# md_v02.net
KiCad netlist of a schematic drawn in EAGLE
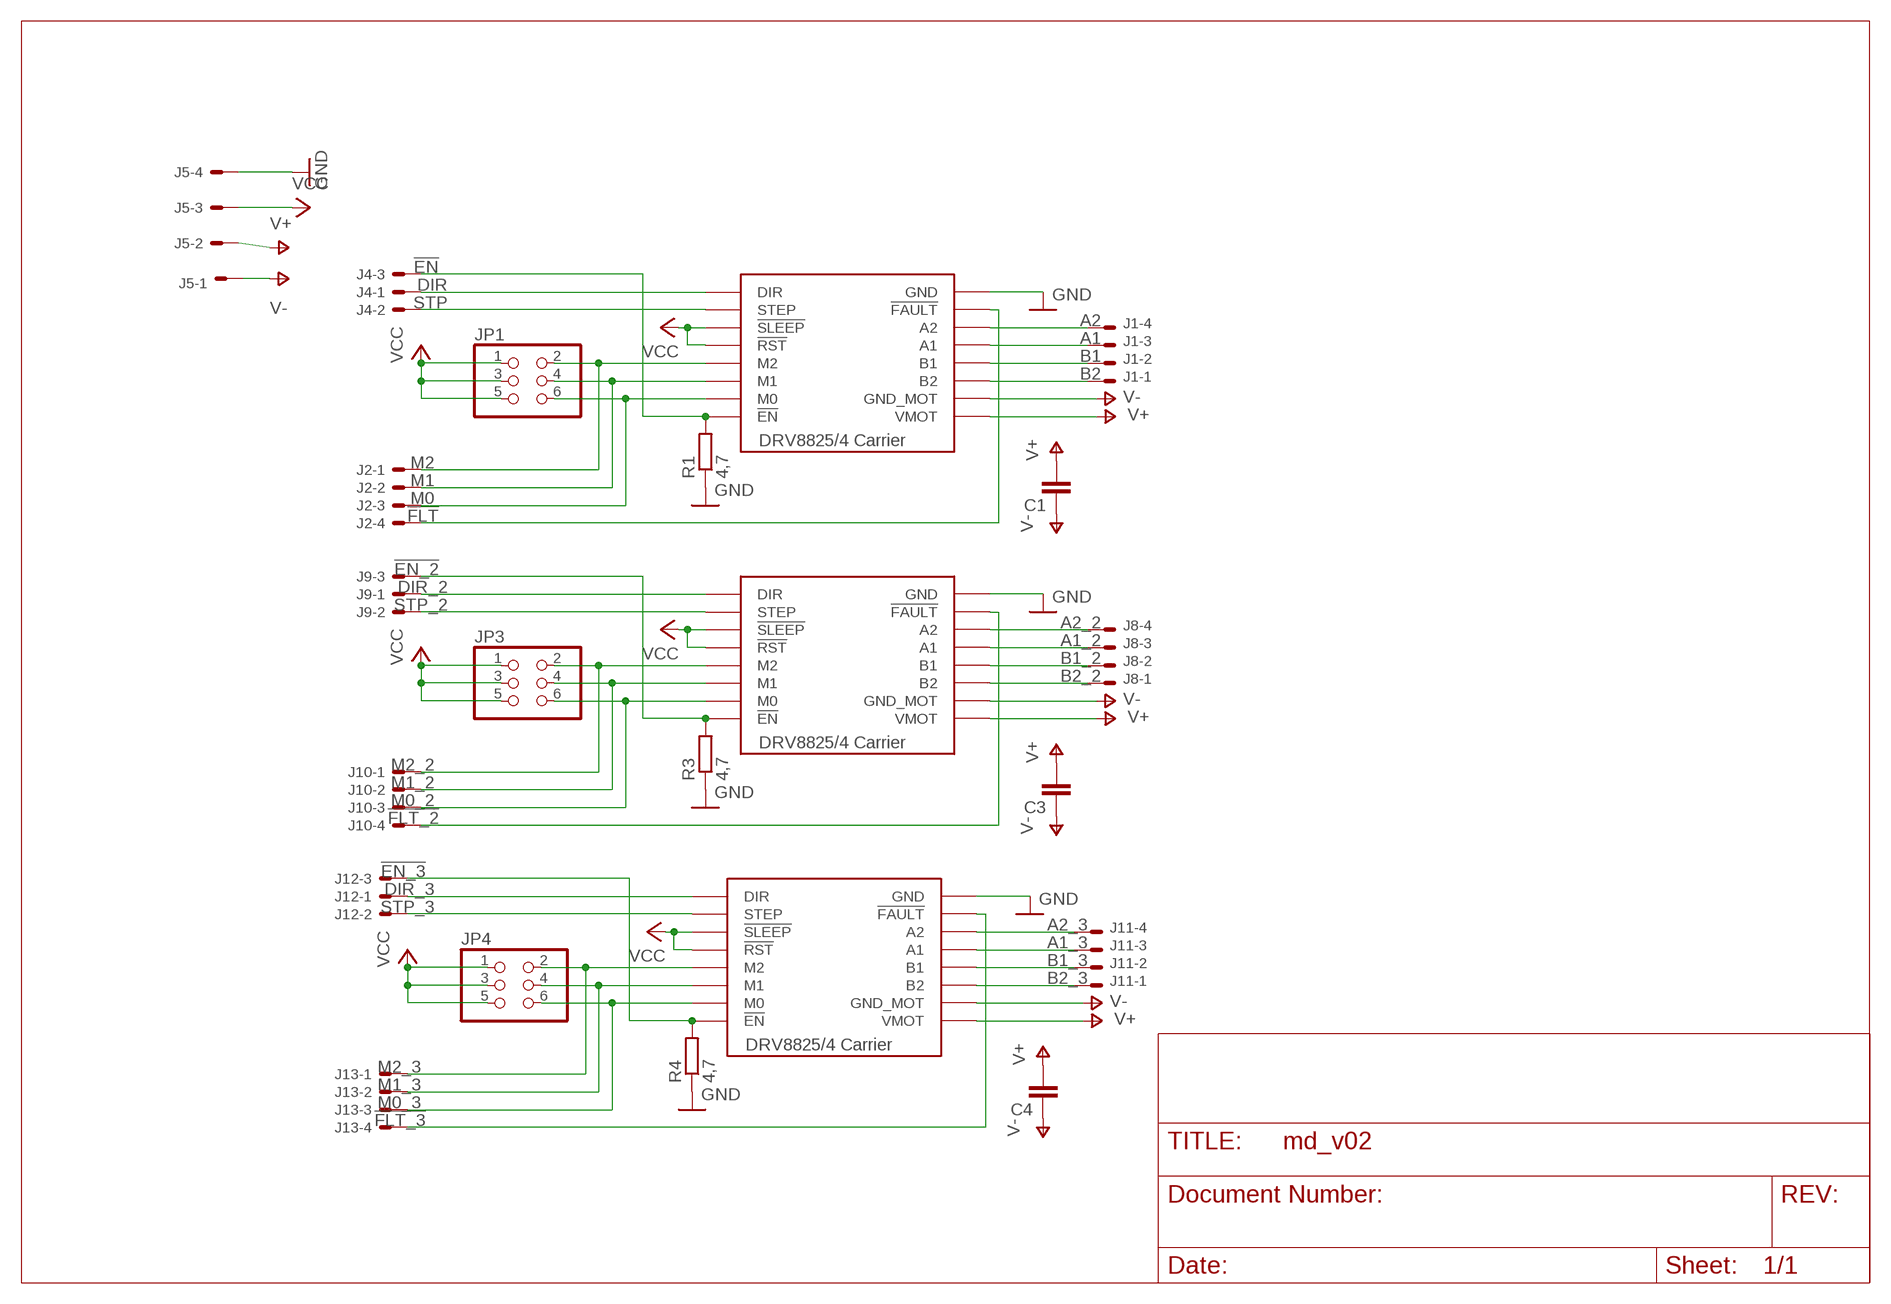
[diagram p0: schematic, sheet 1]

(export (version "E")
  (design (tool "Eeschema 10.0.6"))
  (components
    (comp (ref "C1")
      (value "C-EU050-035X075")
      (footprint "eagle-import:C050-035X075")
      (libsource (lib "eagle-import") (part "C-EU050-035X075"))
    )
    (comp (ref "C3")
      (value "C-EU050-035X075")
      (footprint "eagle-import:C050-035X075")
      (libsource (lib "eagle-import") (part "C-EU050-035X075"))
    )
    (comp (ref "C4")
      (value "C-EU050-035X075")
      (footprint "eagle-import:C050-035X075")
      (libsource (lib "eagle-import") (part "C-EU050-035X075"))
    )
    (comp (ref "J1")
      (value "22-27-2041-04")
      (footprint "eagle-import:6410-04")
      (fields (field (name "MF") "MOLEX"))
      (libsource (lib "eagle-import") (part "22-?-0427-2041"))
    )
    (comp (ref "J2")
      (value "22-27-2041-04")
      (footprint "eagle-import:6410-04")
      (fields (field (name "MF") "MOLEX"))
      (libsource (lib "eagle-import") (part "22-?-0427-2041"))
    )
    (comp (ref "J4")
      (value "22-27-2031-03")
      (footprint "eagle-import:6410-03")
      (fields (field (name "MF") "MOLEX"))
      (libsource (lib "eagle-import") (part "22-?-0327-2031"))
    )
    (comp (ref "J5")
      (value "22-27-2041-04")
      (footprint "eagle-import:6410-04")
      (fields (field (name "MF") "MOLEX"))
      (libsource (lib "eagle-import") (part "22-?-0427-2041"))
    )
    (comp (ref "J8")
      (value "22-27-2041-04")
      (footprint "eagle-import:6410-04")
      (fields (field (name "MF") "MOLEX"))
      (libsource (lib "eagle-import") (part "22-?-0427-2041"))
    )
    (comp (ref "J9")
      (value "22-27-2031-03")
      (footprint "eagle-import:6410-03")
      (fields (field (name "MF") "MOLEX"))
      (libsource (lib "eagle-import") (part "22-?-0327-2031"))
    )
    (comp (ref "J10")
      (value "22-27-2041-04")
      (footprint "eagle-import:6410-04")
      (fields (field (name "MF") "MOLEX"))
      (libsource (lib "eagle-import") (part "22-?-0427-2041"))
    )
    (comp (ref "J11")
      (value "22-27-2041-04")
      (footprint "eagle-import:6410-04")
      (fields (field (name "MF") "MOLEX"))
      (libsource (lib "eagle-import") (part "22-?-0427-2041"))
    )
    (comp (ref "J12")
      (value "22-27-2031-03")
      (footprint "eagle-import:6410-03")
      (fields (field (name "MF") "MOLEX"))
      (libsource (lib "eagle-import") (part "22-?-0327-2031"))
    )
    (comp (ref "J13")
      (value "22-27-2041-04")
      (footprint "eagle-import:6410-04")
      (fields (field (name "MF") "MOLEX"))
      (libsource (lib "eagle-import") (part "22-?-0427-2041"))
    )
    (comp (ref "JP1")
      (value "PINHD-2X3")
      (footprint "eagle-import:2X03")
      (libsource (lib "eagle-import") (part "PINHD-2X3"))
    )
    (comp (ref "JP3")
      (value "PINHD-2X3")
      (footprint "eagle-import:2X03")
      (libsource (lib "eagle-import") (part "PINHD-2X3"))
    )
    (comp (ref "JP4")
      (value "PINHD-2X3")
      (footprint "eagle-import:2X03")
      (libsource (lib "eagle-import") (part "PINHD-2X3"))
    )
    (comp (ref "M1")
      (value "DRV8825_CARRIER\"")
      (footprint "eagle-import:DRV882_CARRIER")
      (libsource (lib "eagle-import") (part "DRV8825_CARRIER{dblquote}"))
    )
    (comp (ref "M3")
      (value "DRV8825_CARRIER\"")
      (footprint "eagle-import:DRV882_CARRIER")
      (libsource (lib "eagle-import") (part "DRV8825_CARRIER{dblquote}"))
    )
    (comp (ref "M4")
      (value "DRV8825_CARRIER\"")
      (footprint "eagle-import:DRV882_CARRIER")
      (libsource (lib "eagle-import") (part "DRV8825_CARRIER{dblquote}"))
    )
    (comp (ref "R1")
      (value "4,7")
      (footprint "eagle-import:0204_7")
      (libsource (lib "eagle-import") (part "R-EU_0204/7"))
    )
    (comp (ref "R3")
      (value "4,7")
      (footprint "eagle-import:0204_7")
      (libsource (lib "eagle-import") (part "R-EU_0204/7"))
    )
    (comp (ref "R4")
      (value "4,7")
      (footprint "eagle-import:0204_7")
      (libsource (lib "eagle-import") (part "R-EU_0204/7"))
    )
  )
  (nets
    (net (code "1") (name "/A1") (class "Default")
      (node (ref "J1") (pin "3") (pinfunction "S_3") (pintype "passive"))
      (node (ref "M1") (pin "A1") (pinfunction "A1_A1") (pintype "output"))
    )
    (net (code "2") (name "/A1_2") (class "Default")
      (node (ref "J8") (pin "3") (pinfunction "S_3") (pintype "passive"))
      (node (ref "M3") (pin "A1") (pinfunction "A1_A1") (pintype "output"))
    )
    (net (code "3") (name "/A1_3") (class "Default")
      (node (ref "J11") (pin "3") (pinfunction "S_3") (pintype "passive"))
      (node (ref "M4") (pin "A1") (pinfunction "A1_A1") (pintype "output"))
    )
    (net (code "4") (name "/A2") (class "Default")
      (node (ref "J1") (pin "4") (pinfunction "S_4") (pintype "passive"))
      (node (ref "M1") (pin "A2") (pinfunction "A2_A2") (pintype "output"))
    )
    (net (code "5") (name "/A2_2") (class "Default")
      (node (ref "J8") (pin "4") (pinfunction "S_4") (pintype "passive"))
      (node (ref "M3") (pin "A2") (pinfunction "A2_A2") (pintype "output"))
    )
    (net (code "6") (name "/A2_3") (class "Default")
      (node (ref "J11") (pin "4") (pinfunction "S_4") (pintype "passive"))
      (node (ref "M4") (pin "A2") (pinfunction "A2_A2") (pintype "output"))
    )
    (net (code "7") (name "/B1") (class "Default")
      (node (ref "J1") (pin "2") (pinfunction "S_2") (pintype "passive"))
      (node (ref "M1") (pin "B1") (pinfunction "B1_B1") (pintype "output"))
    )
    (net (code "8") (name "/B1_2") (class "Default")
      (node (ref "J8") (pin "2") (pinfunction "S_2") (pintype "passive"))
      (node (ref "M3") (pin "B1") (pinfunction "B1_B1") (pintype "output"))
    )
    (net (code "9") (name "/B1_3") (class "Default")
      (node (ref "J11") (pin "2") (pinfunction "S_2") (pintype "passive"))
      (node (ref "M4") (pin "B1") (pinfunction "B1_B1") (pintype "output"))
    )
    (net (code "10") (name "/B2") (class "Default")
      (node (ref "J1") (pin "1") (pinfunction "S_1") (pintype "passive"))
      (node (ref "M1") (pin "B2") (pinfunction "B2_B2") (pintype "output"))
    )
    (net (code "11") (name "/B2_2") (class "Default")
      (node (ref "J8") (pin "1") (pinfunction "S_1") (pintype "passive"))
      (node (ref "M3") (pin "B2") (pinfunction "B2_B2") (pintype "output"))
    )
    (net (code "12") (name "/B2_3") (class "Default")
      (node (ref "J11") (pin "1") (pinfunction "S_1") (pintype "passive"))
      (node (ref "M4") (pin "B2") (pinfunction "B2_B2") (pintype "output"))
    )
    (net (code "13") (name "/DIR") (class "Default")
      (node (ref "J4") (pin "1") (pinfunction "S_1") (pintype "passive"))
      (node (ref "M1") (pin "DIR") (pinfunction "DIR_DIR") (pintype "input"))
    )
    (net (code "14") (name "/DIR_2") (class "Default")
      (node (ref "J9") (pin "1") (pinfunction "S_1") (pintype "passive"))
      (node (ref "M3") (pin "DIR") (pinfunction "DIR_DIR") (pintype "input"))
    )
    (net (code "15") (name "/DIR_3") (class "Default")
      (node (ref "J12") (pin "1") (pinfunction "S_1") (pintype "passive"))
      (node (ref "M4") (pin "DIR") (pinfunction "DIR_DIR") (pintype "input"))
    )
    (net (code "16") (name "/M0") (class "Default")
      (node (ref "J2") (pin "3") (pinfunction "S_3") (pintype "passive"))
      (node (ref "JP1") (pin "6") (pinfunction "6_6") (pintype "passive"))
      (node (ref "M1") (pin "M0") (pinfunction "M0_M0") (pintype "input"))
    )
    (net (code "17") (name "/M0_2") (class "Default")
      (node (ref "J10") (pin "3") (pinfunction "S_3") (pintype "passive"))
      (node (ref "JP3") (pin "6") (pinfunction "6_6") (pintype "passive"))
      (node (ref "M3") (pin "M0") (pinfunction "M0_M0") (pintype "input"))
    )
    (net (code "18") (name "/M0_3") (class "Default")
      (node (ref "J13") (pin "3") (pinfunction "S_3") (pintype "passive"))
      (node (ref "JP4") (pin "6") (pinfunction "6_6") (pintype "passive"))
      (node (ref "M4") (pin "M0") (pinfunction "M0_M0") (pintype "input"))
    )
    (net (code "19") (name "/M1") (class "Default")
      (node (ref "J2") (pin "2") (pinfunction "S_2") (pintype "passive"))
      (node (ref "JP1") (pin "4") (pinfunction "4_4") (pintype "passive"))
      (node (ref "M1") (pin "M1") (pinfunction "M1_M1") (pintype "input"))
    )
    (net (code "20") (name "/M1_2") (class "Default")
      (node (ref "J10") (pin "2") (pinfunction "S_2") (pintype "passive"))
      (node (ref "JP3") (pin "4") (pinfunction "4_4") (pintype "passive"))
      (node (ref "M3") (pin "M1") (pinfunction "M1_M1") (pintype "input"))
    )
    (net (code "21") (name "/M1_3") (class "Default")
      (node (ref "J13") (pin "2") (pinfunction "S_2") (pintype "passive"))
      (node (ref "JP4") (pin "4") (pinfunction "4_4") (pintype "passive"))
      (node (ref "M4") (pin "M1") (pinfunction "M1_M1") (pintype "input"))
    )
    (net (code "22") (name "/M2") (class "Default")
      (node (ref "J2") (pin "1") (pinfunction "S_1") (pintype "passive"))
      (node (ref "JP1") (pin "2") (pinfunction "2_2") (pintype "passive"))
      (node (ref "M1") (pin "M2") (pinfunction "M2_M2") (pintype "input"))
    )
    (net (code "23") (name "/M2_2") (class "Default")
      (node (ref "J10") (pin "1") (pinfunction "S_1") (pintype "passive"))
      (node (ref "JP3") (pin "2") (pinfunction "2_2") (pintype "passive"))
      (node (ref "M3") (pin "M2") (pinfunction "M2_M2") (pintype "input"))
    )
    (net (code "24") (name "/M2_3") (class "Default")
      (node (ref "J13") (pin "1") (pinfunction "S_1") (pintype "passive"))
      (node (ref "JP4") (pin "2") (pinfunction "2_2") (pintype "passive"))
      (node (ref "M4") (pin "M2") (pinfunction "M2_M2") (pintype "input"))
    )
    (net (code "25") (name "/STP") (class "Default")
      (node (ref "J4") (pin "2") (pinfunction "S_2") (pintype "passive"))
      (node (ref "M1") (pin "STEP") (pinfunction "STEP_STEP") (pintype "input"))
    )
    (net (code "26") (name "/STP_2") (class "Default")
      (node (ref "J9") (pin "2") (pinfunction "S_2") (pintype "passive"))
      (node (ref "M3") (pin "STEP") (pinfunction "STEP_STEP") (pintype "input"))
    )
    (net (code "27") (name "/STP_3") (class "Default")
      (node (ref "J12") (pin "2") (pinfunction "S_2") (pintype "passive"))
      (node (ref "M4") (pin "STEP") (pinfunction "STEP_STEP") (pintype "input"))
    )
    (net (code "28") (name "/~{EN_2}") (class "Default")
      (node (ref "J9") (pin "3") (pinfunction "S_3") (pintype "passive"))
      (node (ref "M3") (pin "EN") (pinfunction "~{EN}_EN") (pintype "input"))
      (node (ref "R3") (pin "2") (pinfunction "2_2") (pintype "passive"))
    )
    (net (code "29") (name "/~{EN_3}") (class "Default")
      (node (ref "J12") (pin "3") (pinfunction "S_3") (pintype "passive"))
      (node (ref "M4") (pin "EN") (pinfunction "~{EN}_EN") (pintype "input"))
      (node (ref "R4") (pin "2") (pinfunction "2_2") (pintype "passive"))
    )
    (net (code "30") (name "/~{EN}") (class "Default")
      (node (ref "J4") (pin "3") (pinfunction "S_3") (pintype "passive"))
      (node (ref "M1") (pin "EN") (pinfunction "~{EN}_EN") (pintype "input"))
      (node (ref "R1") (pin "2") (pinfunction "2_2") (pintype "passive"))
    )
    (net (code "31") (name "/~{FLT_2}") (class "Default")
      (node (ref "J10") (pin "4") (pinfunction "S_4") (pintype "passive"))
      (node (ref "M3") (pin "!FLT") (pinfunction "~{FAULT}_!FLT") (pintype "passive"))
    )
    (net (code "32") (name "/~{FLT_3}") (class "Default")
      (node (ref "J13") (pin "4") (pinfunction "S_4") (pintype "passive"))
      (node (ref "M4") (pin "!FLT") (pinfunction "~{FAULT}_!FLT") (pintype "passive"))
    )
    (net (code "33") (name "/~{FLT}") (class "Default")
      (node (ref "J2") (pin "4") (pinfunction "S_4") (pintype "passive"))
      (node (ref "M1") (pin "!FLT") (pinfunction "~{FAULT}_!FLT") (pintype "passive"))
    )
    (net (code "34") (name "GND") (class "Default")
      (node (ref "J5") (pin "4") (pinfunction "S_4") (pintype "passive"))
      (node (ref "M1") (pin "GND") (pinfunction "GND_GND") (pintype "power_in"))
      (node (ref "M3") (pin "GND") (pinfunction "GND_GND") (pintype "power_in"))
      (node (ref "M4") (pin "GND") (pinfunction "GND_GND") (pintype "power_in"))
      (node (ref "R1") (pin "1") (pinfunction "1_1") (pintype "passive"))
      (node (ref "R3") (pin "1") (pinfunction "1_1") (pintype "passive"))
      (node (ref "R4") (pin "1") (pinfunction "1_1") (pintype "passive"))
    )
    (net (code "35") (name "V+") (class "Default")
      (node (ref "C1") (pin "2") (pinfunction "2_2") (pintype "passive"))
      (node (ref "C3") (pin "2") (pinfunction "2_2") (pintype "passive"))
      (node (ref "C4") (pin "2") (pinfunction "2_2") (pintype "passive"))
      (node (ref "J5") (pin "2") (pinfunction "S_2") (pintype "passive"))
      (node (ref "M1") (pin "VMOT") (pinfunction "VMOT_VMOT") (pintype "power_in"))
      (node (ref "M3") (pin "VMOT") (pinfunction "VMOT_VMOT") (pintype "power_in"))
      (node (ref "M4") (pin "VMOT") (pinfunction "VMOT_VMOT") (pintype "power_in"))
    )
    (net (code "36") (name "V-") (class "Default")
      (node (ref "C1") (pin "1") (pinfunction "1_1") (pintype "passive"))
      (node (ref "C3") (pin "1") (pinfunction "1_1") (pintype "passive"))
      (node (ref "C4") (pin "1") (pinfunction "1_1") (pintype "passive"))
      (node (ref "J5") (pin "1") (pinfunction "S_1") (pintype "passive"))
      (node (ref "M1") (pin "GND_MOT") (pinfunction "GND_MOT_GND_MOT") (pintype "power_in"))
      (node (ref "M3") (pin "GND_MOT") (pinfunction "GND_MOT_GND_MOT") (pintype "power_in"))
      (node (ref "M4") (pin "GND_MOT") (pinfunction "GND_MOT_GND_MOT") (pintype "power_in"))
    )
    (net (code "37") (name "VCC") (class "Default")
      (node (ref "J5") (pin "3") (pinfunction "S_3") (pintype "passive"))
      (node (ref "JP1") (pin "1") (pinfunction "1_1") (pintype "passive"))
      (node (ref "JP1") (pin "3") (pinfunction "3_3") (pintype "passive"))
      (node (ref "JP1") (pin "5") (pinfunction "5_5") (pintype "passive"))
      (node (ref "JP3") (pin "1") (pinfunction "1_1") (pintype "passive"))
      (node (ref "JP3") (pin "3") (pinfunction "3_3") (pintype "passive"))
      (node (ref "JP3") (pin "5") (pinfunction "5_5") (pintype "passive"))
      (node (ref "JP4") (pin "1") (pinfunction "1_1") (pintype "passive"))
      (node (ref "JP4") (pin "3") (pinfunction "3_3") (pintype "passive"))
      (node (ref "JP4") (pin "5") (pinfunction "5_5") (pintype "passive"))
      (node (ref "M1") (pin "RST") (pinfunction "~{RST}_RST") (pintype "input"))
      (node (ref "M1") (pin "SLP") (pinfunction "~{SLEEP}_SLP") (pintype "input"))
      (node (ref "M3") (pin "RST") (pinfunction "~{RST}_RST") (pintype "input"))
      (node (ref "M3") (pin "SLP") (pinfunction "~{SLEEP}_SLP") (pintype "input"))
      (node (ref "M4") (pin "RST") (pinfunction "~{RST}_RST") (pintype "input"))
      (node (ref "M4") (pin "SLP") (pinfunction "~{SLEEP}_SLP") (pintype "input"))
    )
  )
)
